# 3__STM32F103.net
KiCad netlist of a schematic drawn in Altium Designer
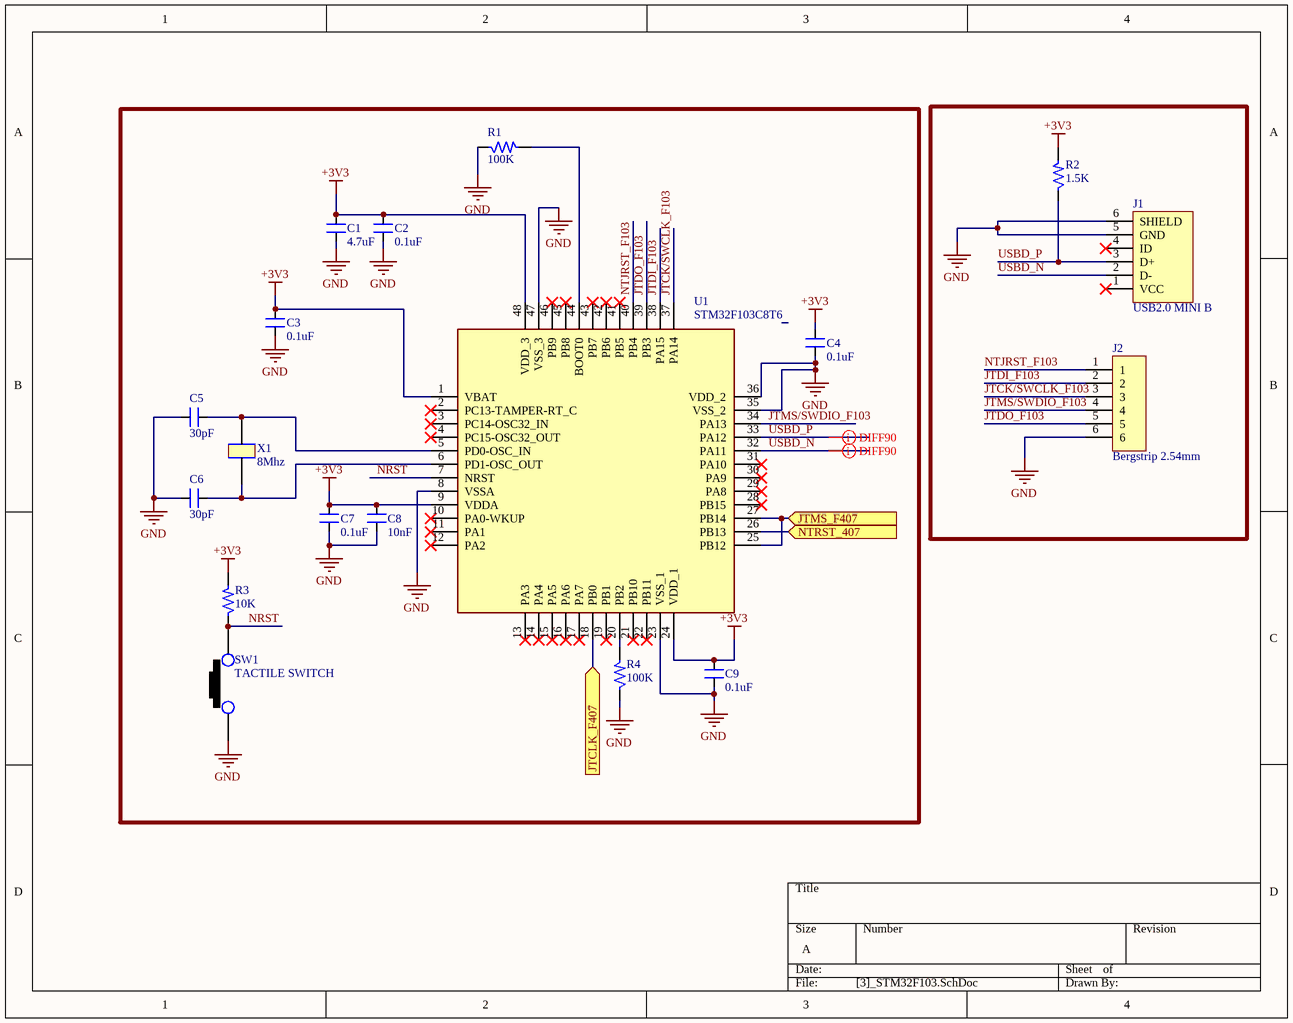
[diagram p0: [3]_STM32F103.SchDoc]

(export (version "E")
  (design (tool "Eeschema 10.0.6"))
  (components
    (comp (ref "C1")
      (value "4.7uF")
      (footprint "CAP_0805")
      (description "4.7µF ±10% 50V Ceramic Capacitor X5R 0805 (2012 Metric)")
      (fields
        (field (name "MANUFACTURER") "Yageo")
        (field (name "MANUFACTURER PART NUMBER") "GRM21BR61H475KE51L")
      )
      (libsource (lib "ESTEEMPCBLIB") (part "CAP_4.7uF-50V-10%-0805"))
    )
    (comp (ref "C2")
      (value "0.1uF")
      (footprint "CAP_0805")
      (description "0.1µF ±10% 50V Ceramic Capacitor X7R 0805 (2012 Metric)")
      (fields
        (field (name "MANUFACTURER") "Samsung")
        (field (name "MANUFACTURER PART NUMBER") "CL21B104KBCNNNC")
      )
      (libsource (lib "ESTEEMPCBLIB") (part "CAP_0.1uF-50V-10%-0805"))
    )
    (comp (ref "C3")
      (value "0.1uF")
      (footprint "CAP_0805")
      (description "0.1µF ±10% 50V Ceramic Capacitor X7R 0805 (2012 Metric)")
      (fields
        (field (name "MANUFACTURER") "Samsung")
        (field (name "MANUFACTURER PART NUMBER") "CL21B104KBCNNNC")
      )
      (libsource (lib "ESTEEMPCBLIB") (part "CAP_0.1uF-50V-10%-0805"))
    )
    (comp (ref "C4")
      (value "0.1uF")
      (footprint "CAP_0805")
      (description "0.1µF ±10% 50V Ceramic Capacitor X7R 0805 (2012 Metric)")
      (fields
        (field (name "MANUFACTURER") "Samsung")
        (field (name "MANUFACTURER PART NUMBER") "CL21B104KBCNNNC")
      )
      (libsource (lib "ESTEEMPCBLIB") (part "CAP_0.1uF-50V-10%-0805"))
    )
    (comp (ref "C5")
      (value "30pF")
      (footprint "CAP_0805")
      (description "±10% 50V Ceramic Capacitor C0G, NP0 0805 (2012 Metric)")
      (fields
        (field (name "MANUFACTURER PART NUMBER") "C0805C300K5GAC7800")
        (field (name "MANUFACTURER") "KEMET")
      )
      (libsource (lib "ESTEEMPCBLIB") (part "CAP_30pF-50V-10%-0805"))
    )
    (comp (ref "C6")
      (value "30pF")
      (footprint "CAP_0805")
      (description "±10% 50V Ceramic Capacitor C0G, NP0 0805 (2012 Metric)")
      (fields
        (field (name "MANUFACTURER PART NUMBER") "C0805C300K5GAC7800")
        (field (name "MANUFACTURER") "KEMET")
      )
      (libsource (lib "ESTEEMPCBLIB") (part "CAP_30pF-50V-10%-0805"))
    )
    (comp (ref "C7")
      (value "0.1uF")
      (footprint "CAP_0805")
      (description "0.1µF ±5% 50V Ceramic Capacitor X7R 0805 (2012 Metric)")
      (fields
        (field (name "MANUFACTURER") "AVX Corporation")
        (field (name "MANUFACTURER PART NUMBER") "08055C104JAT4A")
      )
      (libsource (lib "ESTEEMPCBLIB") (part "CAP_0.1uF-50V-5%-0805"))
    )
    (comp (ref "C8")
      (value "10nF")
      (footprint "CAP_0805")
      (description "10000pF ±10% 50V Ceramic Capacitor X7R 0805 (2012 Metric)")
      (fields
        (field (name "MANUFACTURER") "Samsung")
        (field (name "MANUFACTURER PART NUMBER") "C0805C103K5RECAUTO")
      )
      (libsource (lib "ESTEEMPCBLIB") (part "CAP_10nF-50V-10%-0805"))
    )
    (comp (ref "C9")
      (value "0.1uF")
      (footprint "CAP_0805")
      (description "0.1µF ±10% 50V Ceramic Capacitor X7R 0805 (2012 Metric)")
      (fields
        (field (name "MANUFACTURER") "Samsung")
        (field (name "MANUFACTURER PART NUMBER") "CL21B104KBCNNNC")
      )
      (libsource (lib "ESTEEMPCBLIB") (part "CAP_0.1uF-50V-10%-0805"))
    )
    (comp (ref "J1")
      (value "USB2.0 MINI B")
      (footprint "CON_690-005-299-043")
      (description "USB - mini B USB 2.0 Receptacle Connector 5 Position Surface Mount, Right Angle")
      (fields
        (field (name "MANUFACTURER") "EDAC")
        (field (name "MANUFACTURER PART NUMBER") "690-005-299-043")
      )
      (libsource (lib "ESTEEMPCBLIB") (part "CON_USB2.0-MINIB-SMD"))
    )
    (comp (ref "J2")
      (value "Bergstrip 2.54mm")
      (footprint "CON6_100_59D78_TH_ST")
      (description "6 Pins, 1 Row 2.54mm Pitch, Straight bergstrip, Female")
      (fields (field (name "MANUFACTURER") "Molex") (field (name "MANUFACTURER PART NUMBER") "22-10-2061"))
      (libsource (lib "ESTEEMPCBLIB") (part "CON-BS-SKT_6X1-100-ST-TH"))
    )
    (comp (ref "R1")
      (value "100K")
      (footprint "RES_0603")
      (description "100 kOhms ±1% 0.1W, 1/10W Chip Resistor 0603 (1608 Metric) Automotive AEC-Q200 Thick Film")
      (fields
        (field (name "MANUFACTURER") "Stackpole Electronics")
        (field (name "MANUFACTURER PART NUMBER") "RMCF0603FT100K")
      )
      (libsource (lib "ESTEEMPCBLIB") (part "RES_100K-0.1W-1%-0603"))
    )
    (comp (ref "R2")
      (value "1.5K")
      (footprint "RES_0805")
      (description "1.5 kOhms ±1% 0.125W, 1/8W Chip Resistor 0805 (2012 Metric) Thick Film")
      (fields
        (field (name "MANUFACTURER") "TE Connectivity Passive Product")
        (field (name "MANUFACTURER PART NUMBER") "CRG0805F1K5")
      )
      (libsource (lib "ESTEEMPCBLIB") (part "RES_1.5K-0.125W-1%-0805"))
    )
    (comp (ref "R3")
      (value "10K")
      (footprint "RES_0603")
      (description "10 kOhms ±1% 0.1W, 1/10W Chip Resistor 0603 (1608 Metric) Automotive AEC-Q200 Thick Film")
      (fields (field (name "MANUFACTURER") "Walsin") (field (name "MANUFACTURER PART NUMBER") "WR06X1002FTL"))
      (libsource (lib "ESTEEMPCBLIB") (part "RES_10K-0.1W-1%-0603"))
    )
    (comp (ref "R4")
      (value "100K")
      (footprint "RES_0603")
      (description "100 kOhms ±1% 0.1W, 1/10W Chip Resistor 0603 (1608 Metric) Automotive AEC-Q200 Thick Film")
      (fields
        (field (name "MANUFACTURER") "Stackpole Electronics")
        (field (name "MANUFACTURER PART NUMBER") "RMCF0603FT100K")
      )
      (libsource (lib "ESTEEMPCBLIB") (part "RES_100K-0.1W-1%-0603"))
    )
    (comp (ref "SW1")
      (value "TACTILE SWITCH")
      (footprint "SW_342_SMD")
      (description "Tactile Switch SPST-NO Top Actuated Surface Mount")
      (fields
        (field (name "MANUFACTURER") "ITT C&K")
        (field (name "MANUFACTURER PART NUMBER") "RS-282G05A3-SMRT")
      )
      (libsource (lib "ESTEEMPCBLIB") (part "SW1_RS-282G05A3-SMRT-SMD"))
    )
    (comp (ref "U1")
      (value "STM32F103C8T6")
      (footprint "LQFP-48_19.6_393_58X11_SMD")
      (description "ARM® Cortex®-M3 STM32F1 Microcontroller IC 32-Bit 72MHz 64KB (64K x 8) FLASH 48-LQFP (7x7)")
      (fields (field (name "MANUFACTURER") "STMicroelectronics"))
      (libsource (lib "ESTEEMPCBLIB") (part "IC_STM32F103C8T6"))
    )
    (comp (ref "X1")
      (value "8Mhz")
      (footprint "XTAL_314_240X47_SMD")
      (description "8MHz ±30ppm Crystal 32pF 60 Ohms HC-49/US")
      (fields
        (field (name "MANUFACTURER") "Fox Electronics")
        (field (name "MANUFACTURER PART NUMBER") "ECS-80-32-5PX-TR")
      )
      (libsource (lib "ESTEEMPCBLIB") (part "XTAL_8MHZ-ECS-80-32-5PX-SMD"))
    )
  )
  (nets
    (net (code "1") (name "+3V3") (class "Default")
      (node (ref "C1") (pin "2") (pinfunction "2_2") (pintype "passive"))
      (node (ref "C2") (pin "2") (pinfunction "2_2") (pintype "passive"))
      (node (ref "C3") (pin "2") (pinfunction "2_2") (pintype "passive"))
      (node (ref "C4") (pin "2") (pinfunction "2_2") (pintype "passive"))
      (node (ref "C7") (pin "2") (pinfunction "2_2") (pintype "passive"))
      (node (ref "C8") (pin "2") (pinfunction "2_2") (pintype "passive"))
      (node (ref "C9") (pin "2") (pinfunction "2_2") (pintype "passive"))
      (node (ref "R2") (pin "2") (pinfunction "2_2") (pintype "passive"))
      (node (ref "R3") (pin "2") (pinfunction "2_2") (pintype "passive"))
      (node (ref "U1") (pin "1") (pinfunction "VBAT_1") (pintype "passive"))
      (node (ref "U1") (pin "24") (pinfunction "VDD_1_24") (pintype "passive"))
      (node (ref "U1") (pin "48") (pinfunction "VDD_3_48") (pintype "passive"))
      (node (ref "U1") (pin "9") (pinfunction "VDDA_9") (pintype "passive"))
    )
    (net (code "2") (name "/JTCK{slash}SWCLK_F103") (class "Default")
      (node (ref "J2") (pin "3") (pinfunction "3_3") (pintype "passive"))
      (node (ref "U1") (pin "37") (pinfunction "PA14_37") (pintype "passive"))
    )
    (net (code "3") (name "/JTCLK_F407") (class "Default")
      (node (ref "U1") (pin "18") (pinfunction "PB0_18") (pintype "passive"))
    )
    (net (code "4") (name "/JTDI_F103") (class "Default")
      (node (ref "J2") (pin "2") (pinfunction "2_2") (pintype "passive"))
      (node (ref "U1") (pin "38") (pinfunction "PA15_38") (pintype "passive"))
    )
    (net (code "5") (name "/JTDO_F103") (class "Default")
      (node (ref "J2") (pin "5") (pinfunction "5_5") (pintype "passive"))
      (node (ref "U1") (pin "39") (pinfunction "PB3_39") (pintype "passive"))
    )
    (net (code "6") (name "/JTMS_F407") (class "Default")
      (node (ref "U1") (pin "25") (pinfunction "PB12_25") (pintype "passive"))
      (node (ref "U1") (pin "27") (pinfunction "PB14_27") (pintype "passive"))
    )
    (net (code "7") (name "/JTMS{slash}SWDIO_F103") (class "Default")
      (node (ref "J2") (pin "4") (pinfunction "4_4") (pintype "passive"))
      (node (ref "U1") (pin "34") (pinfunction "PA13_34") (pintype "passive"))
    )
    (net (code "8") (name "/NRST") (class "Default")
      (node (ref "R3") (pin "1") (pinfunction "1_1") (pintype "passive"))
      (node (ref "SW1") (pin "2") (pinfunction "2_2") (pintype "passive"))
      (node (ref "U1") (pin "7") (pinfunction "NRST_7") (pintype "passive"))
    )
    (net (code "9") (name "/NTJRST_F103") (class "Default")
      (node (ref "J2") (pin "1") (pinfunction "1_1") (pintype "passive"))
      (node (ref "U1") (pin "40") (pinfunction "PB4_40") (pintype "passive"))
    )
    (net (code "10") (name "/NTRST_407") (class "Default")
      (node (ref "U1") (pin "26") (pinfunction "PB13_26") (pintype "passive"))
    )
    (net (code "11") (name "/USBD_N") (class "Default")
      (node (ref "J1") (pin "2") (pinfunction "D-_2") (pintype "passive"))
      (node (ref "U1") (pin "32") (pinfunction "PA11_32") (pintype "passive"))
    )
    (net (code "12") (name "/USBD_P") (class "Default")
      (node (ref "J1") (pin "3") (pinfunction "D+_3") (pintype "passive"))
      (node (ref "R2") (pin "1") (pinfunction "1_1") (pintype "passive"))
      (node (ref "U1") (pin "33") (pinfunction "PA12_33") (pintype "passive"))
    )
    (net (code "13") (name "GND") (class "Default")
      (node (ref "C1") (pin "1") (pinfunction "1_1") (pintype "passive"))
      (node (ref "C2") (pin "1") (pinfunction "1_1") (pintype "passive"))
      (node (ref "C3") (pin "1") (pinfunction "1_1") (pintype "passive"))
      (node (ref "C4") (pin "1") (pinfunction "1_1") (pintype "passive"))
      (node (ref "C5") (pin "2") (pinfunction "2_2") (pintype "passive"))
      (node (ref "C6") (pin "2") (pinfunction "2_2") (pintype "passive"))
      (node (ref "C7") (pin "1") (pinfunction "1_1") (pintype "passive"))
      (node (ref "C8") (pin "1") (pinfunction "1_1") (pintype "passive"))
      (node (ref "C9") (pin "1") (pinfunction "1_1") (pintype "passive"))
      (node (ref "J1") (pin "5") (pinfunction "GND_5") (pintype "passive"))
      (node (ref "J1") (pin "6") (pinfunction "SHIELD_6") (pintype "passive"))
      (node (ref "J2") (pin "6") (pinfunction "6_6") (pintype "passive"))
      (node (ref "R1") (pin "1") (pinfunction "1_1") (pintype "passive"))
      (node (ref "R4") (pin "1") (pinfunction "1_1") (pintype "passive"))
      (node (ref "SW1") (pin "1") (pinfunction "1_1") (pintype "passive"))
      (node (ref "U1") (pin "23") (pinfunction "VSS_1_23") (pintype "passive"))
      (node (ref "U1") (pin "35") (pinfunction "VSS_2_35") (pintype "passive"))
      (node (ref "U1") (pin "36") (pinfunction "VDD_2_36") (pintype "passive"))
      (node (ref "U1") (pin "47") (pinfunction "VSS_3_47") (pintype "passive"))
      (node (ref "U1") (pin "8") (pinfunction "VSSA_8") (pintype "passive"))
    )
    (net (code "14") (name "Net-(U1-BOOT0)") (class "Default")
      (node (ref "R1") (pin "2") (pinfunction "2_2") (pintype "passive"))
      (node (ref "U1") (pin "44") (pinfunction "BOOT0_44") (pintype "passive"))
    )
    (net (code "15") (name "Net-(U1-PB2)") (class "Default")
      (node (ref "R4") (pin "2") (pinfunction "2_2") (pintype "passive"))
      (node (ref "U1") (pin "20") (pinfunction "PB2_20") (pintype "passive"))
    )
    (net (code "16") (name "Net-(U1-PD0-OSC_IN)") (class "Default")
      (node (ref "C5") (pin "1") (pinfunction "1_1") (pintype "passive"))
      (node (ref "U1") (pin "5") (pinfunction "PD0-OSC_IN_5") (pintype "passive"))
      (node (ref "X1") (pin "2") (pinfunction "2_2") (pintype "passive"))
    )
    (net (code "17") (name "Net-(U1-PD1-OSC_OUT)") (class "Default")
      (node (ref "C6") (pin "1") (pinfunction "1_1") (pintype "passive"))
      (node (ref "U1") (pin "6") (pinfunction "PD1-OSC_OUT_6") (pintype "passive"))
      (node (ref "X1") (pin "1") (pinfunction "1_1") (pintype "passive"))
    )
    (net (code "18") (name "unconnected-(J1-ID-Pad4)") (class "Default")
      (node (ref "J1") (pin "4") (pinfunction "ID_4") (pintype "passive+no_connect"))
    )
    (net (code "19") (name "unconnected-(J1-VCC-Pad1)") (class "Default")
      (node (ref "J1") (pin "1") (pinfunction "VCC_1") (pintype "passive+no_connect"))
    )
    (net (code "20") (name "unconnected-(U1-PA0-WKUP-Pad10)") (class "Default")
      (node (ref "U1") (pin "10") (pinfunction "PA0-WKUP_10") (pintype "passive+no_connect"))
    )
    (net (code "21") (name "unconnected-(U1-PA1-Pad11)") (class "Default")
      (node (ref "U1") (pin "11") (pinfunction "PA1_11") (pintype "passive+no_connect"))
    )
    (net (code "22") (name "unconnected-(U1-PA2-Pad12)") (class "Default")
      (node (ref "U1") (pin "12") (pinfunction "PA2_12") (pintype "passive+no_connect"))
    )
    (net (code "23") (name "unconnected-(U1-PA3-Pad13)") (class "Default")
      (node (ref "U1") (pin "13") (pinfunction "PA3_13") (pintype "passive+no_connect"))
    )
    (net (code "24") (name "unconnected-(U1-PA4-Pad14)") (class "Default")
      (node (ref "U1") (pin "14") (pinfunction "PA4_14") (pintype "passive+no_connect"))
    )
    (net (code "25") (name "unconnected-(U1-PA5-Pad15)") (class "Default")
      (node (ref "U1") (pin "15") (pinfunction "PA5_15") (pintype "passive+no_connect"))
    )
    (net (code "26") (name "unconnected-(U1-PA6-Pad16)") (class "Default")
      (node (ref "U1") (pin "16") (pinfunction "PA6_16") (pintype "passive+no_connect"))
    )
    (net (code "27") (name "unconnected-(U1-PA7-Pad17)") (class "Default")
      (node (ref "U1") (pin "17") (pinfunction "PA7_17") (pintype "passive+no_connect"))
    )
    (net (code "28") (name "unconnected-(U1-PA8-Pad29)") (class "Default")
      (node (ref "U1") (pin "29") (pinfunction "PA8_29") (pintype "passive+no_connect"))
    )
    (net (code "29") (name "unconnected-(U1-PA9-Pad30)") (class "Default")
      (node (ref "U1") (pin "30") (pinfunction "PA9_30") (pintype "passive+no_connect"))
    )
    (net (code "30") (name "unconnected-(U1-PA10-Pad31)") (class "Default")
      (node (ref "U1") (pin "31") (pinfunction "PA10_31") (pintype "passive+no_connect"))
    )
    (net (code "31") (name "unconnected-(U1-PB1-Pad19)") (class "Default")
      (node (ref "U1") (pin "19") (pinfunction "PB1_19") (pintype "passive+no_connect"))
    )
    (net (code "32") (name "unconnected-(U1-PB5-Pad41)") (class "Default")
      (node (ref "U1") (pin "41") (pinfunction "PB5_41") (pintype "passive+no_connect"))
    )
    (net (code "33") (name "unconnected-(U1-PB6-Pad42)") (class "Default")
      (node (ref "U1") (pin "42") (pinfunction "PB6_42") (pintype "passive+no_connect"))
    )
    (net (code "34") (name "unconnected-(U1-PB7-Pad43)") (class "Default")
      (node (ref "U1") (pin "43") (pinfunction "PB7_43") (pintype "passive+no_connect"))
    )
    (net (code "35") (name "unconnected-(U1-PB8-Pad45)") (class "Default")
      (node (ref "U1") (pin "45") (pinfunction "PB8_45") (pintype "passive+no_connect"))
    )
    (net (code "36") (name "unconnected-(U1-PB9-Pad46)") (class "Default")
      (node (ref "U1") (pin "46") (pinfunction "PB9_46") (pintype "passive+no_connect"))
    )
    (net (code "37") (name "unconnected-(U1-PB10-Pad21)") (class "Default")
      (node (ref "U1") (pin "21") (pinfunction "PB10_21") (pintype "passive+no_connect"))
    )
    (net (code "38") (name "unconnected-(U1-PB11-Pad22)") (class "Default")
      (node (ref "U1") (pin "22") (pinfunction "PB11_22") (pintype "passive+no_connect"))
    )
    (net (code "39") (name "unconnected-(U1-PB15-Pad28)") (class "Default")
      (node (ref "U1") (pin "28") (pinfunction "PB15_28") (pintype "passive+no_connect"))
    )
    (net (code "40") (name "unconnected-(U1-PC13-TAMPER-RT_C-Pad2)") (class "Default")
      (node (ref "U1") (pin "2") (pinfunction "PC13-TAMPER-RT_C_2") (pintype "passive+no_connect"))
    )
    (net (code "41") (name "unconnected-(U1-PC14-OSC32_IN-Pad3)") (class "Default")
      (node (ref "U1") (pin "3") (pinfunction "PC14-OSC32_IN_3") (pintype "passive+no_connect"))
    )
    (net (code "42") (name "unconnected-(U1-PC15-OSC32_OUT-Pad4)") (class "Default")
      (node (ref "U1") (pin "4") (pinfunction "PC15-OSC32_OUT_4") (pintype "passive+no_connect"))
    )
  )
)
